# SController-8833.net
KiCad netlist of a schematic drawn in EAGLE
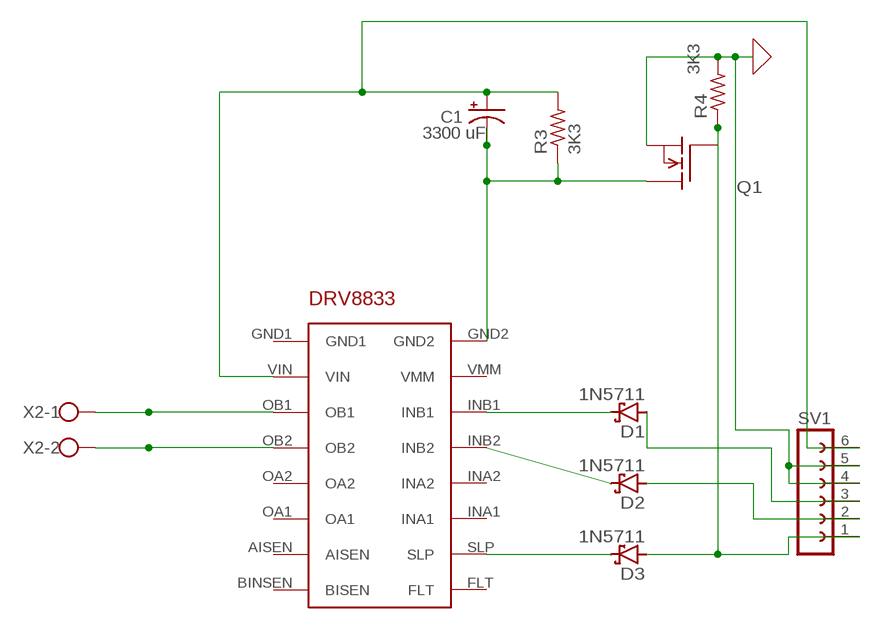
[diagram p0: schematic, sheet 1]

(export (version "E")
  (design (tool "Eeschema 10.0.6"))
  (components
    (comp (ref "\"\"")
      (value "POLOLU-DRV8833")
      (footprint "eagle-import:POLOLU-DRV8833")
      (libsource (lib "eagle-import") (part "POLOLU-DRV8833"))
    )
    (comp (ref "C1")
      (value "3300 uF")
      (footprint "eagle-import:E5-10,5")
      (libsource (lib "eagle-import") (part "CPOL-USE5-10.5"))
    )
    (comp (ref "D1")
      (value "1N5711")
      (footprint "eagle-import:F126Z12")
      (libsource (lib "eagle-import") (part "SCHOTTKY-DIODEF126Z12"))
    )
    (comp (ref "D2")
      (value "1N5711")
      (footprint "eagle-import:F126Z12")
      (libsource (lib "eagle-import") (part "SCHOTTKY-DIODEF126Z12"))
    )
    (comp (ref "D3")
      (value "1N5711")
      (footprint "eagle-import:F126Z12")
      (libsource (lib "eagle-import") (part "SCHOTTKY-DIODEF126Z12"))
    )
    (comp (ref "Q1")
      (value "SUP75N06-08")
      (footprint "eagle-import:TO220")
      (libsource (lib "eagle-import") (part "SUP75N06-08"))
    )
    (comp (ref "R3")
      (value "3K3")
      (footprint "eagle-import:0204_7")
      (libsource (lib "eagle-import") (part "R-US_0204/7"))
    )
    (comp (ref "R4")
      (value "R-US_0204/7")
      (footprint "eagle-import:0204_7")
      (fields (field (name "SPICEPREFIX") "R") (field (name "SPICEPREFIX_1") "3K3"))
      (libsource (lib "eagle-import") (part "R-US_0204/7"))
    )
    (comp (ref "SV1")
      (value "FE06-1")
      (footprint "eagle-import:FE06")
      (libsource (lib "eagle-import") (part "FE06-1"))
    )
    (comp (ref "X2")
      (value "W237-102")
      (footprint "eagle-import:W237-102")
      (fields (field (name "MPN") "237-102"))
      (libsource (lib "eagle-import") (part "W237-102"))
    )
  )
  (nets
    (net (code "1") (name "GND") (class "Default")
      (node (ref "Q1") (pin "3") (pinfunction "S_3") (pintype "passive"))
      (node (ref "R4") (pin "2") (pinfunction "2_2") (pintype "passive"))
      (node (ref "SV1") (pin "4") (pinfunction "4_4") (pintype "passive"))
      (node (ref "SV1") (pin "5") (pinfunction "5_5") (pintype "passive"))
    )
    (net (code "2") (name "Net-(\"\"-PadINB1)") (class "Default")
      (node (ref "\"\"") (pin "INB1") (pinfunction "INB1_INB1") (pintype "bidirectional"))
      (node (ref "D1") (pin "C") (pinfunction "C_C") (pintype "passive"))
    )
    (net (code "3") (name "Net-(\"\"-PadINB2)") (class "Default")
      (node (ref "\"\"") (pin "INB2") (pinfunction "INB2_INB2") (pintype "bidirectional"))
      (node (ref "D2") (pin "C") (pinfunction "C_C") (pintype "passive"))
    )
    (net (code "4") (name "Net-(\"\"-PadSLP)") (class "Default")
      (node (ref "\"\"") (pin "SLP") (pinfunction "SLP_SLP") (pintype "bidirectional"))
      (node (ref "D3") (pin "C") (pinfunction "C_C") (pintype "passive"))
    )
    (net (code "5") (name "Net-(\"\"-PadVIN)") (class "Default")
      (node (ref "\"\"") (pin "VIN") (pinfunction "VIN_VIN") (pintype "bidirectional"))
      (node (ref "C1") (pin "+") (pinfunction "+_+") (pintype "passive"))
      (node (ref "R3") (pin "2") (pinfunction "2_2") (pintype "passive"))
      (node (ref "SV1") (pin "6") (pinfunction "6_6") (pintype "passive"))
    )
    (net (code "6") (name "Net-(D1-PadA)") (class "Default")
      (node (ref "D1") (pin "A") (pinfunction "A_A") (pintype "passive"))
      (node (ref "SV1") (pin "3") (pinfunction "3_3") (pintype "passive"))
    )
    (net (code "7") (name "Net-(D2-PadA)") (class "Default")
      (node (ref "D2") (pin "A") (pinfunction "A_A") (pintype "passive"))
      (node (ref "SV1") (pin "2") (pinfunction "2_2") (pintype "passive"))
    )
    (net (code "8") (name "Net-(Q1-D)") (class "Default")
      (node (ref "\"\"") (pin "GND2") (pinfunction "GND2_GND2") (pintype "bidirectional"))
      (node (ref "C1") (pin "-") (pinfunction "-_-") (pintype "passive"))
      (node (ref "Q1") (pin "2") (pinfunction "D_2") (pintype "passive"))
      (node (ref "R3") (pin "1") (pinfunction "1_1") (pintype "passive"))
    )
    (net (code "9") (name "Net-(Q1-G)") (class "Default")
      (node (ref "D3") (pin "A") (pinfunction "A_A") (pintype "passive"))
      (node (ref "Q1") (pin "1") (pinfunction "G_1") (pintype "passive"))
      (node (ref "R4") (pin "1") (pinfunction "1_1") (pintype "passive"))
      (node (ref "SV1") (pin "1") (pinfunction "1_1") (pintype "passive"))
    )
    (net (code "10") (name "Net-(X2A-KL)") (class "Default")
      (node (ref "\"\"") (pin "OB1") (pinfunction "OB1_OB1") (pintype "bidirectional"))
      (node (ref "X2") (pin "1") (pinfunction "KL_1") (pintype "passive"))
    )
    (net (code "11") (name "Net-(X2B-KL)") (class "Default")
      (node (ref "\"\"") (pin "OB2") (pinfunction "OB2_OB2") (pintype "bidirectional"))
      (node (ref "X2") (pin "2") (pinfunction "KL_2") (pintype "passive"))
    )
    (net (code "12") (name "unconnected-(\"\"-BISEN-PadBINSEN)") (class "Default")
      (node (ref "\"\"") (pin "BINSEN") (pinfunction "BISEN_BINSEN") (pintype "bidirectional"))
    )
    (net (code "13") (name "unconnected-(\"\"-PadAISEN)") (class "Default")
      (node (ref "\"\"") (pin "AISEN") (pinfunction "AISEN_AISEN") (pintype "bidirectional"))
    )
    (net (code "14") (name "unconnected-(\"\"-PadFLT)") (class "Default")
      (node (ref "\"\"") (pin "FLT") (pinfunction "FLT_FLT") (pintype "bidirectional"))
    )
    (net (code "15") (name "unconnected-(\"\"-PadGND1)") (class "Default")
      (node (ref "\"\"") (pin "GND1") (pinfunction "GND1_GND1") (pintype "bidirectional"))
    )
    (net (code "16") (name "unconnected-(\"\"-PadINA1)") (class "Default")
      (node (ref "\"\"") (pin "INA1") (pinfunction "INA1_INA1") (pintype "bidirectional"))
    )
    (net (code "17") (name "unconnected-(\"\"-PadINA2)") (class "Default")
      (node (ref "\"\"") (pin "INA2") (pinfunction "INA2_INA2") (pintype "bidirectional"))
    )
    (net (code "18") (name "unconnected-(\"\"-PadOA1)") (class "Default")
      (node (ref "\"\"") (pin "OA1") (pinfunction "OA1_OA1") (pintype "bidirectional"))
    )
    (net (code "19") (name "unconnected-(\"\"-PadOA2)") (class "Default")
      (node (ref "\"\"") (pin "OA2") (pinfunction "OA2_OA2") (pintype "bidirectional"))
    )
    (net (code "20") (name "unconnected-(\"\"-PadVMM)") (class "Default")
      (node (ref "\"\"") (pin "VMM") (pinfunction "VMM_VMM") (pintype "output"))
    )
  )
)
